# 3_relayoutv4.net
KiCad netlist of a schematic drawn in Altium Designer
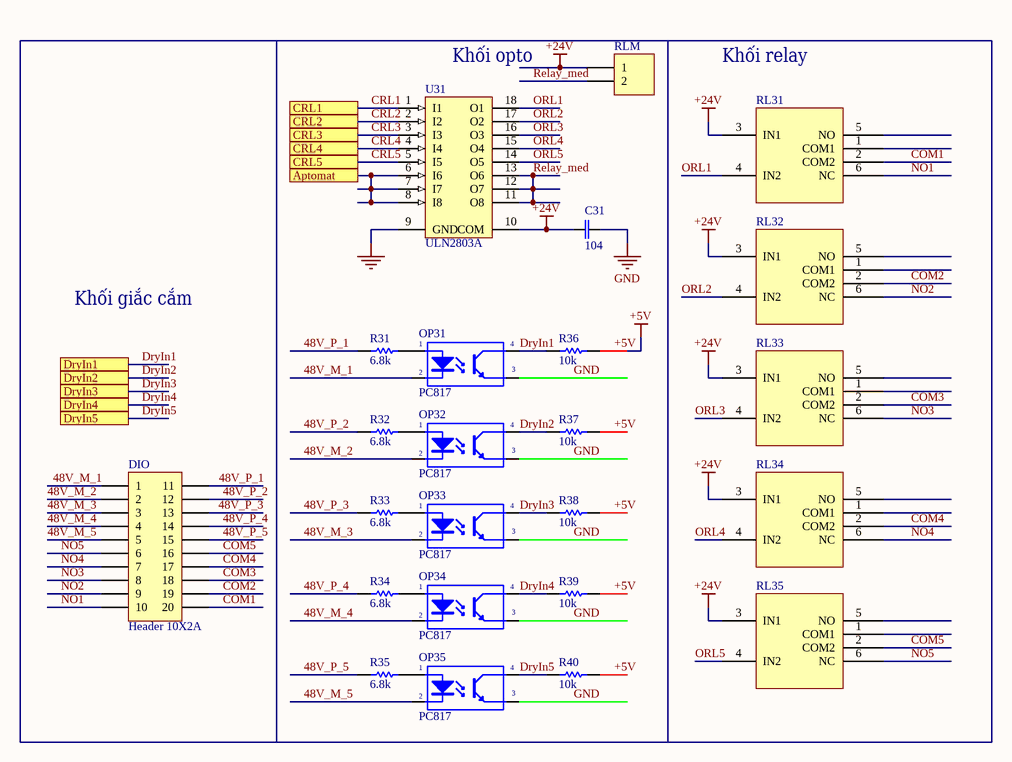
[diagram p0: 3.relayoutv4.SchDoc]

(export (version "E")
  (design (tool "Eeschema 10.0.6"))
  (components
    (comp (ref "C31")
      (value "104")
      (footprint "swatpcblib:CAP 0805")
      (description "Capacitor non polarized")
      (fields (field (name "Comment") "Tụ điện dán 0805104"))
      (libsource (lib "swatpcblib") (part "CAP NP"))
    )
    (comp (ref "DIO")
      (value "Header 10X2A")
      (footprint "heromap:HDR2X10_CEN")
      (description "Header, 10-Pin, Dual row")
      (fields (field (name "PUBLISHER") "Altium Limited"))
      (libsource (lib "heromap") (part "Header 10X2A"))
    )
    (comp (ref "OP31")
      (value "PC817")
      (footprint "hayqua:DIP4/W0.3")
      (description "Single Opto")
      (libsource (lib "syhaunguyen") (part "PC817"))
    )
    (comp (ref "OP32")
      (value "PC817")
      (footprint "hayqua:DIP4/W0.3")
      (description "Single Opto")
      (libsource (lib "syhaunguyen") (part "PC817"))
    )
    (comp (ref "OP33")
      (value "PC817")
      (footprint "hayqua:DIP4/W0.3")
      (description "Single Opto")
      (libsource (lib "syhaunguyen") (part "PC817"))
    )
    (comp (ref "OP34")
      (value "PC817")
      (footprint "hayqua:DIP4/W0.3")
      (description "Single Opto")
      (libsource (lib "syhaunguyen") (part "PC817"))
    )
    (comp (ref "OP35")
      (value "PC817")
      (footprint "hayqua:DIP4/W0.3")
      (description "Single Opto")
      (libsource (lib "syhaunguyen") (part "PC817"))
    )
    (comp (ref "R31")
      (value "6.8k")
      (footprint "PBL - SMD Packages:RESC3216N")
      (description "Resistor")
      (fields (field (name "Comment") "Điện trở dán 12066.8k"))
      (libsource (lib "swatpcblib") (part "Res"))
    )
    (comp (ref "R32")
      (value "6.8k")
      (footprint "PBL - SMD Packages:RESC3216N")
      (description "Resistor")
      (fields (field (name "Comment") "Điện trở dán 12066.8k"))
      (libsource (lib "swatpcblib") (part "Res"))
    )
    (comp (ref "R33")
      (value "6.8k")
      (footprint "PBL - SMD Packages:RESC3216N")
      (description "Resistor")
      (fields (field (name "Comment") "Điện trở dán 12066.8k"))
      (libsource (lib "swatpcblib") (part "Res"))
    )
    (comp (ref "R34")
      (value "6.8k")
      (footprint "PBL - SMD Packages:RESC3216N")
      (description "Resistor")
      (fields (field (name "Comment") "Điện trở dán 12066.8k"))
      (libsource (lib "swatpcblib") (part "Res"))
    )
    (comp (ref "R35")
      (value "6.8k")
      (footprint "PBL - SMD Packages:RESC3216N")
      (description "Resistor")
      (fields (field (name "Comment") "Điện trở dán 12066.8k"))
      (libsource (lib "swatpcblib") (part "Res"))
    )
    (comp (ref "R36")
      (value "10k")
      (footprint "swatpcblib:RES 0805")
      (description "Resistor")
      (fields (field (name "Comment") "Điện trở dán 080510k"))
      (libsource (lib "swatpcblib") (part "Res"))
    )
    (comp (ref "R37")
      (value "10k")
      (footprint "swatpcblib:RES 0805")
      (description "Resistor")
      (fields (field (name "Comment") "Điện trở dán 080510k"))
      (libsource (lib "swatpcblib") (part "Res"))
    )
    (comp (ref "R38")
      (value "10k")
      (footprint "swatpcblib:RES 0805")
      (description "Resistor")
      (fields (field (name "Comment") "Điện trở dán 080510k"))
      (libsource (lib "swatpcblib") (part "Res"))
    )
    (comp (ref "R39")
      (value "10k")
      (footprint "swatpcblib:RES 0805")
      (description "Resistor")
      (fields (field (name "Comment") "Điện trở dán 080510k"))
      (libsource (lib "swatpcblib") (part "Res"))
    )
    (comp (ref "R40")
      (value "10k")
      (footprint "swatpcblib:RES 0805")
      (description "Resistor")
      (fields (field (name "Comment") "Điện trở dán 080510k"))
      (libsource (lib "swatpcblib") (part "Res"))
    )
    (comp (ref "RL31") (value "HK4100F_12V") (footprint "HK4100F") (libsource (lib "Tuan") (part "HK4100F")))
    (comp (ref "RL32") (value "HK4100F_12V") (footprint "HK4100F") (libsource (lib "Tuan") (part "HK4100F")))
    (comp (ref "RL33") (value "HK4100F_12V") (footprint "HK4100F") (libsource (lib "Tuan") (part "HK4100F")))
    (comp (ref "RL34") (value "HK4100F_12V") (footprint "HK4100F") (libsource (lib "Tuan") (part "HK4100F")))
    (comp (ref "RL35") (value "HK4100F_12V") (footprint "HK4100F") (libsource (lib "Tuan") (part "HK4100F")))
    (comp (ref "RLM")
      (value "Header 2")
      (footprint "heromap:HDR1X2")
      (description "Header, 2-Pin")
      (fields (field (name "PUBLISHER") "Altium Limited"))
      (libsource (lib "heromap") (part "Header 2"))
    )
    (comp (ref "U31")
      (value "ULN2803A")
      (footprint "SOIC-18")
      (description "High-Voltage, High-Current Darlington Array")
      (fields (field (name "PUBLISHER") "Altium Limited"))
      (libsource (lib "syhaunguyen") (part "ULN2803A"))
    )
  )
  (nets
    (net (code "1") (name "+5V") (class "Default")
      (node (ref "R36") (pin "2") (pinfunction "2_2") (pintype "passive"))
      (node (ref "R37") (pin "2") (pinfunction "2_2") (pintype "passive"))
      (node (ref "R38") (pin "2") (pinfunction "2_2") (pintype "passive"))
      (node (ref "R39") (pin "2") (pinfunction "2_2") (pintype "passive"))
      (node (ref "R40") (pin "2") (pinfunction "2_2") (pintype "passive"))
    )
    (net (code "2") (name "+24V") (class "Default")
      (node (ref "C31") (pin "2") (pinfunction "2_2") (pintype "passive"))
      (node (ref "RL31") (pin "3") (pinfunction "IN1_3") (pintype "passive"))
      (node (ref "RL32") (pin "3") (pinfunction "IN1_3") (pintype "passive"))
      (node (ref "RL33") (pin "3") (pinfunction "IN1_3") (pintype "passive"))
      (node (ref "RL34") (pin "3") (pinfunction "IN1_3") (pintype "passive"))
      (node (ref "RL35") (pin "3") (pinfunction "IN1_3") (pintype "passive"))
      (node (ref "RLM") (pin "1") (pinfunction "1_1") (pintype "passive"))
      (node (ref "U31") (pin "10") (pinfunction "COM_10") (pintype "passive"))
    )
    (net (code "3") (name "/48V_M_1") (class "Default")
      (node (ref "DIO") (pin "1") (pinfunction "1_1") (pintype "passive"))
      (node (ref "OP31") (pin "2") (pinfunction "K_2") (pintype "passive"))
    )
    (net (code "4") (name "/48V_M_2") (class "Default")
      (node (ref "DIO") (pin "2") (pinfunction "2_2") (pintype "passive"))
      (node (ref "OP32") (pin "2") (pinfunction "K_2") (pintype "passive"))
    )
    (net (code "5") (name "/48V_M_3") (class "Default")
      (node (ref "DIO") (pin "3") (pinfunction "3_3") (pintype "passive"))
      (node (ref "OP33") (pin "2") (pinfunction "K_2") (pintype "passive"))
    )
    (net (code "6") (name "/48V_M_4") (class "Default")
      (node (ref "DIO") (pin "4") (pinfunction "4_4") (pintype "passive"))
      (node (ref "OP34") (pin "2") (pinfunction "K_2") (pintype "passive"))
    )
    (net (code "7") (name "/48V_M_5") (class "Default")
      (node (ref "DIO") (pin "5") (pinfunction "5_5") (pintype "passive"))
      (node (ref "OP35") (pin "2") (pinfunction "K_2") (pintype "passive"))
    )
    (net (code "8") (name "/48V_P_1") (class "Default")
      (node (ref "DIO") (pin "11") (pinfunction "11_11") (pintype "passive"))
      (node (ref "R31") (pin "1") (pinfunction "1_1") (pintype "passive"))
    )
    (net (code "9") (name "/48V_P_2") (class "Default")
      (node (ref "DIO") (pin "12") (pinfunction "12_12") (pintype "passive"))
      (node (ref "R32") (pin "1") (pinfunction "1_1") (pintype "passive"))
    )
    (net (code "10") (name "/48V_P_3") (class "Default")
      (node (ref "DIO") (pin "13") (pinfunction "13_13") (pintype "passive"))
      (node (ref "R33") (pin "1") (pinfunction "1_1") (pintype "passive"))
    )
    (net (code "11") (name "/48V_P_4") (class "Default")
      (node (ref "DIO") (pin "14") (pinfunction "14_14") (pintype "passive"))
      (node (ref "R34") (pin "1") (pinfunction "1_1") (pintype "passive"))
    )
    (net (code "12") (name "/48V_P_5") (class "Default")
      (node (ref "DIO") (pin "15") (pinfunction "15_15") (pintype "passive"))
      (node (ref "R35") (pin "1") (pinfunction "1_1") (pintype "passive"))
    )
    (net (code "13") (name "/Aptomat") (class "Default")
      (node (ref "U31") (pin "6") (pinfunction "I6_6") (pintype "input"))
      (node (ref "U31") (pin "7") (pinfunction "I7_7") (pintype "input"))
      (node (ref "U31") (pin "8") (pinfunction "I8_8") (pintype "input"))
    )
    (net (code "14") (name "/COM1") (class "Default")
      (node (ref "DIO") (pin "20") (pinfunction "20_20") (pintype "passive"))
      (node (ref "RL31") (pin "2") (pinfunction "COM2_2") (pintype "passive"))
    )
    (net (code "15") (name "/COM2") (class "Default")
      (node (ref "DIO") (pin "19") (pinfunction "19_19") (pintype "passive"))
      (node (ref "RL32") (pin "2") (pinfunction "COM2_2") (pintype "passive"))
    )
    (net (code "16") (name "/COM3") (class "Default")
      (node (ref "DIO") (pin "18") (pinfunction "18_18") (pintype "passive"))
      (node (ref "RL33") (pin "2") (pinfunction "COM2_2") (pintype "passive"))
    )
    (net (code "17") (name "/COM4") (class "Default")
      (node (ref "DIO") (pin "17") (pinfunction "17_17") (pintype "passive"))
      (node (ref "RL34") (pin "2") (pinfunction "COM2_2") (pintype "passive"))
    )
    (net (code "18") (name "/COM5") (class "Default")
      (node (ref "DIO") (pin "16") (pinfunction "16_16") (pintype "passive"))
      (node (ref "RL35") (pin "2") (pinfunction "COM2_2") (pintype "passive"))
    )
    (net (code "19") (name "/CRL1") (class "Default")
      (node (ref "U31") (pin "1") (pinfunction "I1_1") (pintype "input"))
    )
    (net (code "20") (name "/CRL2") (class "Default")
      (node (ref "U31") (pin "2") (pinfunction "I2_2") (pintype "input"))
    )
    (net (code "21") (name "/CRL3") (class "Default")
      (node (ref "U31") (pin "3") (pinfunction "I3_3") (pintype "input"))
    )
    (net (code "22") (name "/CRL4") (class "Default")
      (node (ref "U31") (pin "4") (pinfunction "I4_4") (pintype "input"))
    )
    (net (code "23") (name "/CRL5") (class "Default")
      (node (ref "U31") (pin "5") (pinfunction "I5_5") (pintype "input"))
    )
    (net (code "24") (name "/DryIn1") (class "Default")
      (node (ref "OP31") (pin "4") (pinfunction "C_4") (pintype "passive"))
      (node (ref "R36") (pin "1") (pinfunction "1_1") (pintype "passive"))
    )
    (net (code "25") (name "/DryIn2") (class "Default")
      (node (ref "OP32") (pin "4") (pinfunction "C_4") (pintype "passive"))
      (node (ref "R37") (pin "1") (pinfunction "1_1") (pintype "passive"))
    )
    (net (code "26") (name "/DryIn3") (class "Default")
      (node (ref "OP33") (pin "4") (pinfunction "C_4") (pintype "passive"))
      (node (ref "R38") (pin "1") (pinfunction "1_1") (pintype "passive"))
    )
    (net (code "27") (name "/DryIn4") (class "Default")
      (node (ref "OP34") (pin "4") (pinfunction "C_4") (pintype "passive"))
      (node (ref "R39") (pin "1") (pinfunction "1_1") (pintype "passive"))
    )
    (net (code "28") (name "/DryIn5") (class "Default")
      (node (ref "OP35") (pin "4") (pinfunction "C_4") (pintype "passive"))
      (node (ref "R40") (pin "1") (pinfunction "1_1") (pintype "passive"))
    )
    (net (code "29") (name "/NO1") (class "Default")
      (node (ref "DIO") (pin "10") (pinfunction "10_10") (pintype "passive"))
      (node (ref "RL31") (pin "6") (pinfunction "NC_6") (pintype "passive"))
    )
    (net (code "30") (name "/NO2") (class "Default")
      (node (ref "DIO") (pin "9") (pinfunction "9_9") (pintype "passive"))
      (node (ref "RL32") (pin "6") (pinfunction "NC_6") (pintype "passive"))
    )
    (net (code "31") (name "/NO3") (class "Default")
      (node (ref "DIO") (pin "8") (pinfunction "8_8") (pintype "passive"))
      (node (ref "RL33") (pin "6") (pinfunction "NC_6") (pintype "passive"))
    )
    (net (code "32") (name "/NO4") (class "Default")
      (node (ref "DIO") (pin "7") (pinfunction "7_7") (pintype "passive"))
      (node (ref "RL34") (pin "6") (pinfunction "NC_6") (pintype "passive"))
    )
    (net (code "33") (name "/NO5") (class "Default")
      (node (ref "DIO") (pin "6") (pinfunction "6_6") (pintype "passive"))
      (node (ref "RL35") (pin "6") (pinfunction "NC_6") (pintype "passive"))
    )
    (net (code "34") (name "/ORL1") (class "Default")
      (node (ref "RL31") (pin "4") (pinfunction "IN2_4") (pintype "passive"))
      (node (ref "U31") (pin "18") (pinfunction "O1_18") (pintype "open_collector"))
    )
    (net (code "35") (name "/ORL2") (class "Default")
      (node (ref "RL32") (pin "4") (pinfunction "IN2_4") (pintype "passive"))
      (node (ref "U31") (pin "17") (pinfunction "O2_17") (pintype "open_collector"))
    )
    (net (code "36") (name "/ORL3") (class "Default")
      (node (ref "RL33") (pin "4") (pinfunction "IN2_4") (pintype "passive"))
      (node (ref "U31") (pin "16") (pinfunction "O3_16") (pintype "open_collector"))
    )
    (net (code "37") (name "/ORL4") (class "Default")
      (node (ref "RL34") (pin "4") (pinfunction "IN2_4") (pintype "passive"))
      (node (ref "U31") (pin "15") (pinfunction "O4_15") (pintype "open_collector"))
    )
    (net (code "38") (name "/ORL5") (class "Default")
      (node (ref "RL35") (pin "4") (pinfunction "IN2_4") (pintype "passive"))
      (node (ref "U31") (pin "14") (pinfunction "O5_14") (pintype "open_collector"))
    )
    (net (code "39") (name "/Relay_med") (class "Default")
      (node (ref "RLM") (pin "2") (pinfunction "2_2") (pintype "passive"))
      (node (ref "U31") (pin "11") (pinfunction "O8_11") (pintype "open_collector"))
      (node (ref "U31") (pin "12") (pinfunction "O7_12") (pintype "open_collector"))
      (node (ref "U31") (pin "13") (pinfunction "O6_13") (pintype "open_collector"))
    )
    (net (code "40") (name "GND") (class "Default")
      (node (ref "C31") (pin "1") (pinfunction "1_1") (pintype "passive"))
      (node (ref "OP31") (pin "3") (pinfunction "E_3") (pintype "passive"))
      (node (ref "OP32") (pin "3") (pinfunction "E_3") (pintype "passive"))
      (node (ref "OP33") (pin "3") (pinfunction "E_3") (pintype "passive"))
      (node (ref "OP34") (pin "3") (pinfunction "E_3") (pintype "passive"))
      (node (ref "OP35") (pin "3") (pinfunction "E_3") (pintype "passive"))
      (node (ref "U31") (pin "9") (pinfunction "GND_9") (pintype "power_in"))
    )
    (net (code "41") (name "Net-(OP31-A)") (class "Default")
      (node (ref "OP31") (pin "1") (pinfunction "A_1") (pintype "passive"))
      (node (ref "R31") (pin "2") (pinfunction "2_2") (pintype "passive"))
    )
    (net (code "42") (name "Net-(OP32-A)") (class "Default")
      (node (ref "OP32") (pin "1") (pinfunction "A_1") (pintype "passive"))
      (node (ref "R32") (pin "2") (pinfunction "2_2") (pintype "passive"))
    )
    (net (code "43") (name "Net-(OP33-A)") (class "Default")
      (node (ref "OP33") (pin "1") (pinfunction "A_1") (pintype "passive"))
      (node (ref "R33") (pin "2") (pinfunction "2_2") (pintype "passive"))
    )
    (net (code "44") (name "Net-(OP34-A)") (class "Default")
      (node (ref "OP34") (pin "1") (pinfunction "A_1") (pintype "passive"))
      (node (ref "R34") (pin "2") (pinfunction "2_2") (pintype "passive"))
    )
    (net (code "45") (name "Net-(OP35-A)") (class "Default")
      (node (ref "OP35") (pin "1") (pinfunction "A_1") (pintype "passive"))
      (node (ref "R35") (pin "2") (pinfunction "2_2") (pintype "passive"))
    )
    (net (code "46") (name "unconnected-(RL31-COM1-Pad1)") (class "Default")
      (node (ref "RL31") (pin "1") (pinfunction "COM1_1") (pintype "passive"))
    )
    (net (code "47") (name "unconnected-(RL31-NO-Pad5)") (class "Default")
      (node (ref "RL31") (pin "5") (pinfunction "NO_5") (pintype "passive"))
    )
    (net (code "48") (name "unconnected-(RL32-COM1-Pad1)") (class "Default")
      (node (ref "RL32") (pin "1") (pinfunction "COM1_1") (pintype "passive"))
    )
    (net (code "49") (name "unconnected-(RL32-NO-Pad5)") (class "Default")
      (node (ref "RL32") (pin "5") (pinfunction "NO_5") (pintype "passive"))
    )
    (net (code "50") (name "unconnected-(RL33-COM1-Pad1)") (class "Default")
      (node (ref "RL33") (pin "1") (pinfunction "COM1_1") (pintype "passive"))
    )
    (net (code "51") (name "unconnected-(RL33-NO-Pad5)") (class "Default")
      (node (ref "RL33") (pin "5") (pinfunction "NO_5") (pintype "passive"))
    )
    (net (code "52") (name "unconnected-(RL34-COM1-Pad1)") (class "Default")
      (node (ref "RL34") (pin "1") (pinfunction "COM1_1") (pintype "passive"))
    )
    (net (code "53") (name "unconnected-(RL34-NO-Pad5)") (class "Default")
      (node (ref "RL34") (pin "5") (pinfunction "NO_5") (pintype "passive"))
    )
    (net (code "54") (name "unconnected-(RL35-COM1-Pad1)") (class "Default")
      (node (ref "RL35") (pin "1") (pinfunction "COM1_1") (pintype "passive"))
    )
    (net (code "55") (name "unconnected-(RL35-NO-Pad5)") (class "Default")
      (node (ref "RL35") (pin "5") (pinfunction "NO_5") (pintype "passive"))
    )
  )
)
